# SCH_usb_hub_2024-06-24.net
KiCad netlist of a schematic drawn in EasyEDA
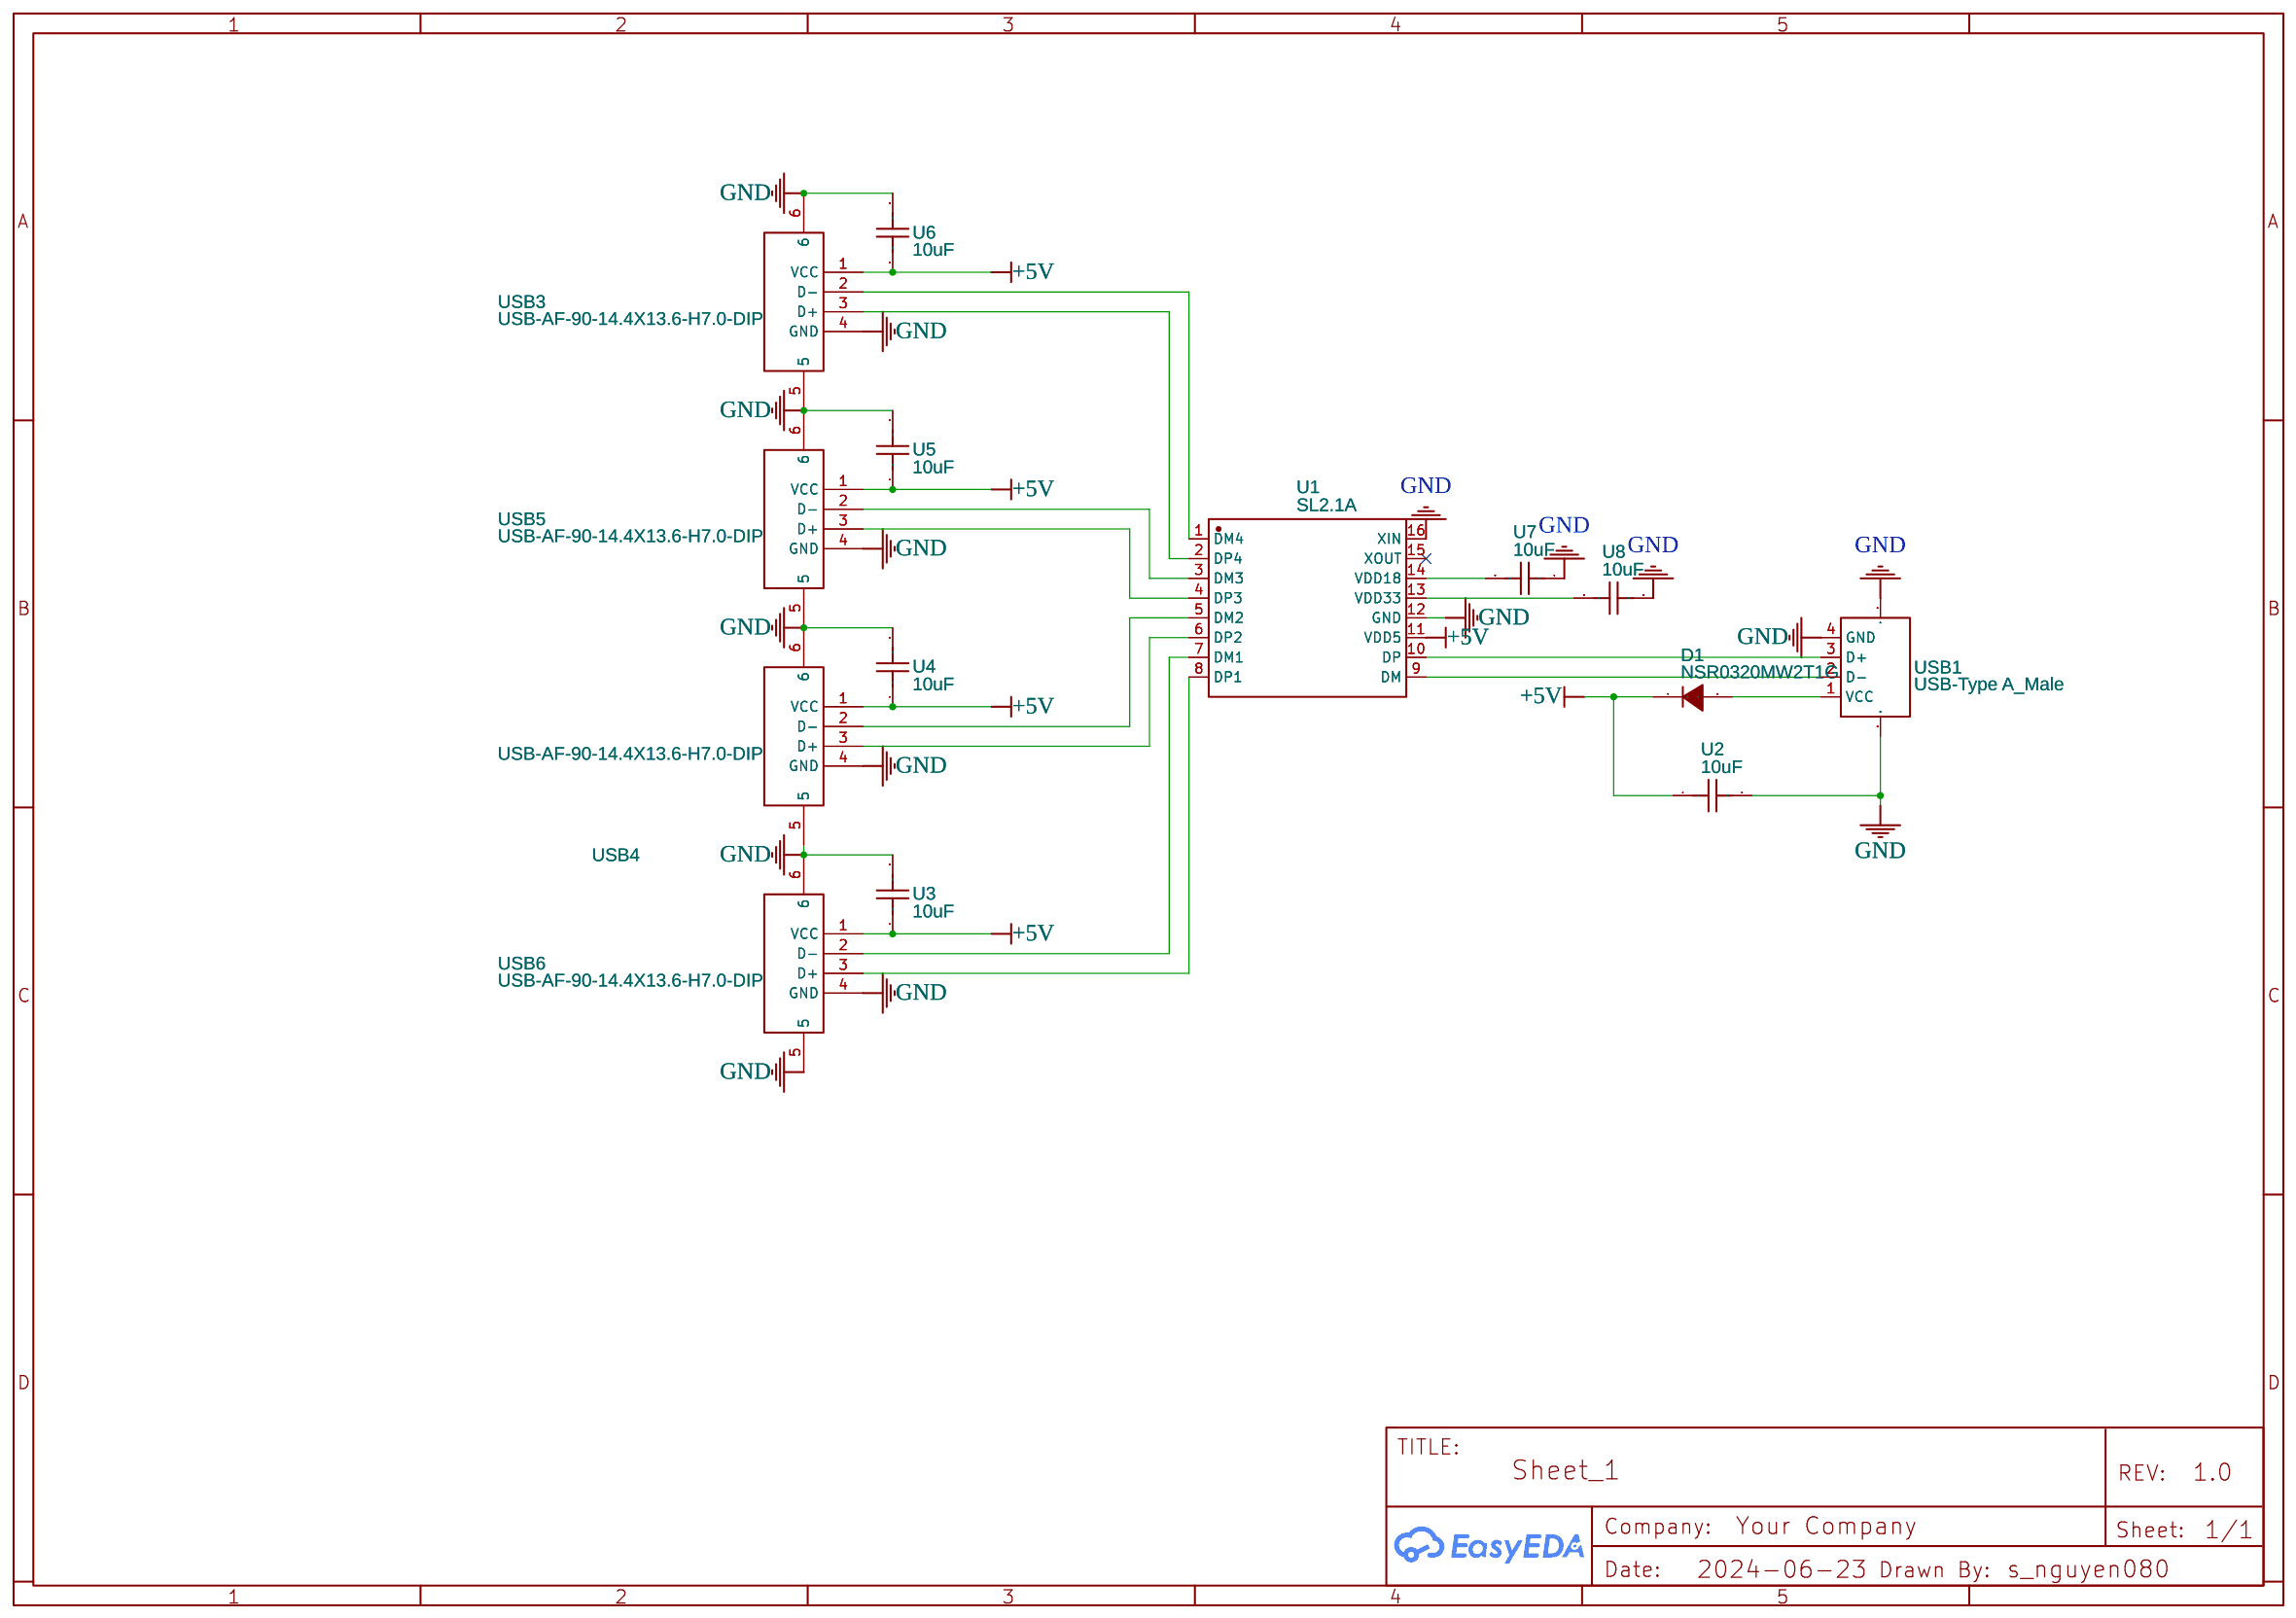
[diagram p0: schematic sheet]

(export (version "E")
  (design (tool "Eeschema 10.0.6"))
  (components
    (comp (ref "D1")
      (value "NSR0320MW2T1G")
      (fields (field (name "Manufacturer") "onsemi(安森美)"))
      (libsource (lib "") (part "NSR0320MW2T1G"))
    )
    (comp (ref "U1")
      (value "SL2.1A")
      (fields (field (name "Manufacturer") "CoreChips(和芯润德)"))
      (libsource (lib "") (part "SL2.1A"))
    )
    (comp (ref "U2")
      (value "10uF")
      (fields (field (name "Manufacturer Part") "0603X106K100CT") (field (name "Manufacturer") "Walsin(华新科)"))
      (libsource (lib "") (part "0603X106K100CT"))
    )
    (comp (ref "U3")
      (value "10uF")
      (fields (field (name "Manufacturer Part") "0603X106K100CT") (field (name "Manufacturer") "Walsin(华新科)"))
      (libsource (lib "") (part "0603X106K100CT_1"))
    )
    (comp (ref "U4")
      (value "10uF")
      (fields (field (name "Manufacturer Part") "0603X106K100CT") (field (name "Manufacturer") "Walsin(华新科)"))
      (libsource (lib "") (part "0603X106K100CT_1"))
    )
    (comp (ref "U5")
      (value "10uF")
      (fields (field (name "Manufacturer Part") "0603X106K100CT") (field (name "Manufacturer") "Walsin(华新科)"))
      (libsource (lib "") (part "0603X106K100CT_1"))
    )
    (comp (ref "U6")
      (value "10uF")
      (fields (field (name "Manufacturer Part") "0603X106K100CT") (field (name "Manufacturer") "Walsin(华新科)"))
      (libsource (lib "") (part "0603X106K100CT_1"))
    )
    (comp (ref "U7")
      (value "10uF")
      (fields (field (name "Manufacturer Part") "0603X106K100CT") (field (name "Manufacturer") "Walsin(华新科)"))
      (libsource (lib "") (part "0603X106K100CT_2"))
    )
    (comp (ref "U8")
      (value "10uF")
      (fields (field (name "Manufacturer Part") "0603X106K100CT") (field (name "Manufacturer") "Walsin(华新科)"))
      (libsource (lib "") (part "0603X106K100CT"))
    )
    (comp (ref "USB1")
      (value "USB-Type A_Male")
      (fields (field (name "Manufacturer Part") "USB-05") (field (name "Manufacturer") "SOFNG"))
      (libsource (lib "") (part "USB-Type A_Male"))
    )
    (comp (ref "USB3")
      (value "USB-AF-90-14.4X13.6-H7.0-DIP")
      (fields (field (name "Manufacturer Part") "903-131A1011D10100") (field (name "Manufacturer") "精拓金"))
      (libsource (lib "") (part "USB-AF-90-14.4X13.6-H7.0-DIP"))
    )
    (comp (ref "USB4")
      (value "USB-AF-90-14.4X13.6-H7.0-DIP")
      (fields (field (name "Manufacturer Part") "903-131A1011D10100") (field (name "Manufacturer") "精拓金"))
      (libsource (lib "") (part "USB-AF-90-14.4X13.6-H7.0-DIP"))
    )
    (comp (ref "USB5")
      (value "USB-AF-90-14.4X13.6-H7.0-DIP")
      (fields (field (name "Manufacturer Part") "903-131A1011D10100") (field (name "Manufacturer") "精拓金"))
      (libsource (lib "") (part "USB-AF-90-14.4X13.6-H7.0-DIP"))
    )
    (comp (ref "USB6")
      (value "USB-AF-90-14.4X13.6-H7.0-DIP")
      (fields (field (name "Manufacturer Part") "903-131A1011D10100") (field (name "Manufacturer") "精拓金"))
      (libsource (lib "") (part "USB-AF-90-14.4X13.6-H7.0-DIP"))
    )
  )
  (nets
    (net (code "1") (name "+5V") (class "Default")
      (node (ref "D1") (pin "1") (pinfunction "C_1") (pintype "unspecified"))
      (node (ref "U1") (pin "11") (pinfunction "VDD5_11") (pintype "unspecified"))
      (node (ref "U2") (pin "1") (pinfunction "1_1") (pintype "unspecified"))
      (node (ref "U3") (pin "1") (pinfunction "1_1") (pintype "unspecified"))
      (node (ref "U4") (pin "1") (pinfunction "1_1") (pintype "unspecified"))
      (node (ref "U5") (pin "1") (pinfunction "1_1") (pintype "unspecified"))
      (node (ref "U6") (pin "1") (pinfunction "1_1") (pintype "unspecified"))
      (node (ref "USB3") (pin "1") (pinfunction "VCC_1") (pintype "unspecified"))
      (node (ref "USB4") (pin "1") (pinfunction "VCC_1") (pintype "unspecified"))
      (node (ref "USB5") (pin "1") (pinfunction "VCC_1") (pintype "unspecified"))
      (node (ref "USB6") (pin "1") (pinfunction "VCC_1") (pintype "unspecified"))
    )
    (net (code "2") (name "GND") (class "Default")
      (node (ref "U1") (pin "12") (pinfunction "GND_12") (pintype "unspecified"))
      (node (ref "U1") (pin "16") (pinfunction "XIN_16") (pintype "unspecified"))
      (node (ref "U2") (pin "2") (pinfunction "2_2") (pintype "unspecified"))
      (node (ref "U3") (pin "2") (pinfunction "2_2") (pintype "unspecified"))
      (node (ref "U4") (pin "2") (pinfunction "2_2") (pintype "unspecified"))
      (node (ref "U5") (pin "2") (pinfunction "2_2") (pintype "unspecified"))
      (node (ref "U6") (pin "2") (pinfunction "2_2") (pintype "unspecified"))
      (node (ref "U7") (pin "1") (pinfunction "1_1") (pintype "unspecified"))
      (node (ref "U8") (pin "2") (pinfunction "2_2") (pintype "unspecified"))
      (node (ref "USB1") (pin "4") (pinfunction "GND_4") (pintype "input"))
      (node (ref "USB1") (pin "5") (pinfunction "5_5") (pintype "unspecified"))
      (node (ref "USB1") (pin "6") (pinfunction "6_6") (pintype "unspecified"))
      (node (ref "USB3") (pin "4") (pinfunction "GND_4") (pintype "unspecified"))
      (node (ref "USB3") (pin "5") (pinfunction "5_5") (pintype "unspecified"))
      (node (ref "USB3") (pin "6") (pinfunction "6_6") (pintype "unspecified"))
      (node (ref "USB4") (pin "4") (pinfunction "GND_4") (pintype "unspecified"))
      (node (ref "USB4") (pin "5") (pinfunction "5_5") (pintype "unspecified"))
      (node (ref "USB4") (pin "6") (pinfunction "6_6") (pintype "unspecified"))
      (node (ref "USB5") (pin "4") (pinfunction "GND_4") (pintype "unspecified"))
      (node (ref "USB5") (pin "5") (pinfunction "5_5") (pintype "unspecified"))
      (node (ref "USB5") (pin "6") (pinfunction "6_6") (pintype "unspecified"))
      (node (ref "USB6") (pin "4") (pinfunction "GND_4") (pintype "unspecified"))
      (node (ref "USB6") (pin "5") (pinfunction "5_5") (pintype "unspecified"))
      (node (ref "USB6") (pin "6") (pinfunction "6_6") (pintype "unspecified"))
    )
    (net (code "3") (name "Net-(D1-A)") (class "Default")
      (node (ref "D1") (pin "2") (pinfunction "A_2") (pintype "unspecified"))
      (node (ref "USB1") (pin "1") (pinfunction "VCC_1") (pintype "input"))
    )
    (net (code "4") (name "Net-(U1-DM)") (class "Default")
      (node (ref "U1") (pin "9") (pinfunction "DM_9") (pintype "unspecified"))
      (node (ref "USB1") (pin "2") (pinfunction "D-_2") (pintype "input"))
    )
    (net (code "5") (name "Net-(U1-DM1)") (class "Default")
      (node (ref "U1") (pin "7") (pinfunction "DM1_7") (pintype "unspecified"))
      (node (ref "USB6") (pin "2") (pinfunction "D-_2") (pintype "unspecified"))
    )
    (net (code "6") (name "Net-(U1-DM2)") (class "Default")
      (node (ref "U1") (pin "5") (pinfunction "DM2_5") (pintype "unspecified"))
      (node (ref "USB4") (pin "2") (pinfunction "D-_2") (pintype "unspecified"))
    )
    (net (code "7") (name "Net-(U1-DM3)") (class "Default")
      (node (ref "U1") (pin "3") (pinfunction "DM3_3") (pintype "unspecified"))
      (node (ref "USB5") (pin "2") (pinfunction "D-_2") (pintype "unspecified"))
    )
    (net (code "8") (name "Net-(U1-DM4)") (class "Default")
      (node (ref "U1") (pin "1") (pinfunction "DM4_1") (pintype "unspecified"))
      (node (ref "USB3") (pin "2") (pinfunction "D-_2") (pintype "unspecified"))
    )
    (net (code "9") (name "Net-(U1-DP)") (class "Default")
      (node (ref "U1") (pin "10") (pinfunction "DP_10") (pintype "unspecified"))
      (node (ref "USB1") (pin "3") (pinfunction "D+_3") (pintype "input"))
    )
    (net (code "10") (name "Net-(U1-DP1)") (class "Default")
      (node (ref "U1") (pin "8") (pinfunction "DP1_8") (pintype "unspecified"))
      (node (ref "USB6") (pin "3") (pinfunction "D+_3") (pintype "unspecified"))
    )
    (net (code "11") (name "Net-(U1-DP2)") (class "Default")
      (node (ref "U1") (pin "6") (pinfunction "DP2_6") (pintype "unspecified"))
      (node (ref "USB4") (pin "3") (pinfunction "D+_3") (pintype "unspecified"))
    )
    (net (code "12") (name "Net-(U1-DP3)") (class "Default")
      (node (ref "U1") (pin "4") (pinfunction "DP3_4") (pintype "unspecified"))
      (node (ref "USB5") (pin "3") (pinfunction "D+_3") (pintype "unspecified"))
    )
    (net (code "13") (name "Net-(U1-DP4)") (class "Default")
      (node (ref "U1") (pin "2") (pinfunction "DP4_2") (pintype "unspecified"))
      (node (ref "USB3") (pin "3") (pinfunction "D+_3") (pintype "unspecified"))
    )
    (net (code "14") (name "Net-(U1-VDD18)") (class "Default")
      (node (ref "U1") (pin "14") (pinfunction "VDD18_14") (pintype "unspecified"))
      (node (ref "U7") (pin "2") (pinfunction "2_2") (pintype "unspecified"))
    )
    (net (code "15") (name "Net-(U1-VDD33)") (class "Default")
      (node (ref "U1") (pin "13") (pinfunction "VDD33_13") (pintype "unspecified"))
      (node (ref "U8") (pin "1") (pinfunction "1_1") (pintype "unspecified"))
    )
    (net (code "16") (name "unconnected-(U1-XOUT-Pad15)") (class "Default")
      (node (ref "U1") (pin "15") (pinfunction "XOUT_15") (pintype "unspecified+no_connect"))
    )
  )
)
